# untitled.net
KiCad netlist of a schematic drawn in EAGLE
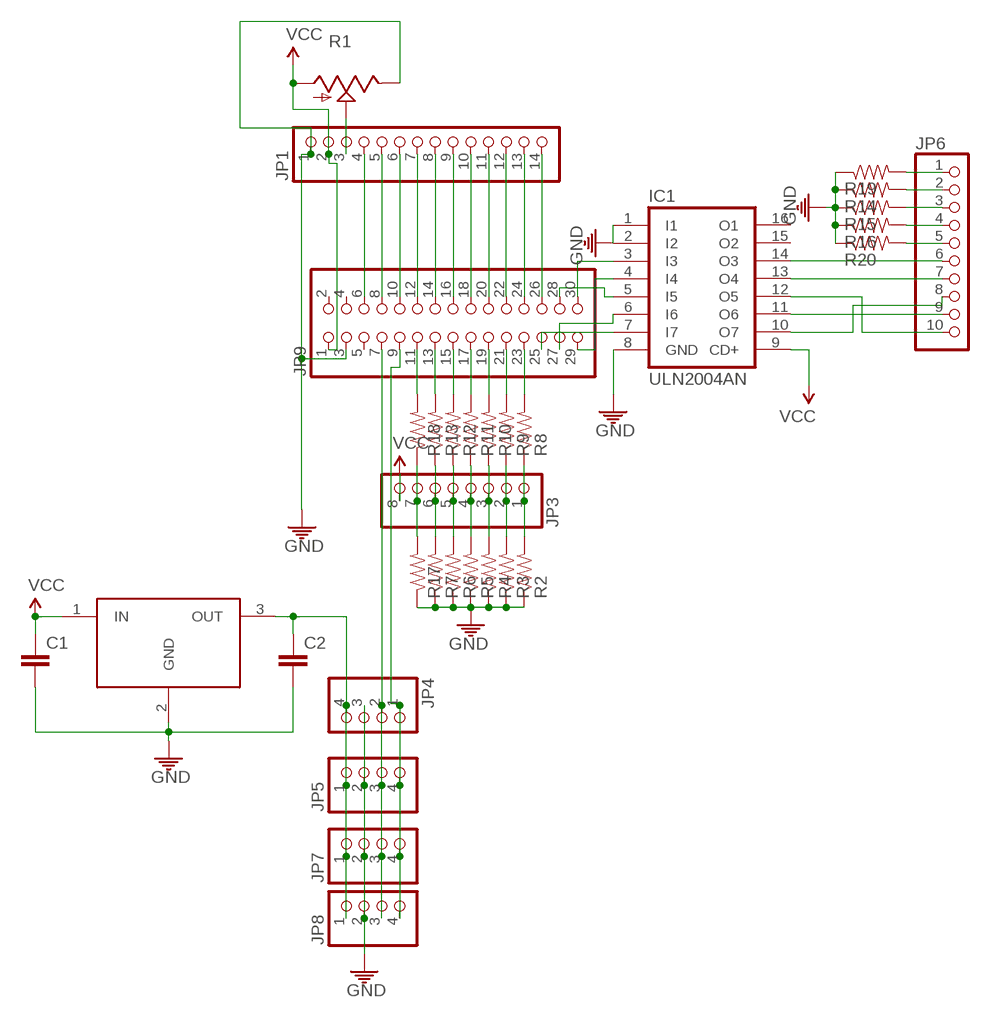
[diagram p0: schematic, sheet 1]

(export (version "E")
  (design (tool "Eeschema 10.0.6"))
  (components
    (comp (ref "C1")
      (value "CAP0805")
      (footprint "eagle-import:0805")
      (libsource (lib "eagle-import") (part "CAP0805"))
    )
    (comp (ref "C2")
      (value "CAP0805")
      (footprint "eagle-import:0805")
      (libsource (lib "eagle-import") (part "CAP0805"))
    )
    (comp (ref "IC1")
      (value "ULN2004AN")
      (footprint "eagle-import:DIL16")
      (libsource (lib "eagle-import") (part "ULN2004AN"))
    )
    (comp (ref "JP1")
      (value "PINHD-1X14")
      (footprint "eagle-import:1X14")
      (libsource (lib "eagle-import") (part "PINHD-1X14"))
    )
    (comp (ref "JP3")
      (value "PINHD-1X8/90")
      (footprint "eagle-import:1X08_90")
      (libsource (lib "eagle-import") (part "PINHD-1X8/90"))
    )
    (comp (ref "JP4")
      (value "PINHD-1X4")
      (footprint "eagle-import:1X04")
      (libsource (lib "eagle-import") (part "PINHD-1X4"))
    )
    (comp (ref "JP5")
      (value "PINHD-1X4")
      (footprint "eagle-import:1X04")
      (libsource (lib "eagle-import") (part "PINHD-1X4"))
    )
    (comp (ref "JP6")
      (value "PINHD-1X10")
      (footprint "eagle-import:1X10")
      (libsource (lib "eagle-import") (part "PINHD-1X10"))
    )
    (comp (ref "JP7")
      (value "PINHD-1X4")
      (footprint "eagle-import:1X04")
      (libsource (lib "eagle-import") (part "PINHD-1X4"))
    )
    (comp (ref "JP8")
      (value "PINHD-1X4")
      (footprint "eagle-import:1X04")
      (libsource (lib "eagle-import") (part "PINHD-1X4"))
    )
    (comp (ref "JP9")
      (value "PINHD-2X15/90")
      (footprint "eagle-import:2X15_90")
      (libsource (lib "eagle-import") (part "PINHD-2X15/90"))
    )
    (comp (ref "R1")
      (value "TRIM_US-B90P")
      (footprint "eagle-import:SP19L")
      (libsource (lib "eagle-import") (part "TRIM_US-B90P"))
    )
    (comp (ref "R2")
      (value "RESISTOR0805-RES")
      (footprint "eagle-import:0805")
      (libsource (lib "eagle-import") (part "RESISTOR0805-RES"))
    )
    (comp (ref "R3")
      (value "RESISTOR0805-RES")
      (footprint "eagle-import:0805")
      (libsource (lib "eagle-import") (part "RESISTOR0805-RES"))
    )
    (comp (ref "R4")
      (value "RESISTOR0805-RES")
      (footprint "eagle-import:0805")
      (libsource (lib "eagle-import") (part "RESISTOR0805-RES"))
    )
    (comp (ref "R5")
      (value "RESISTOR0805-RES")
      (footprint "eagle-import:0805")
      (libsource (lib "eagle-import") (part "RESISTOR0805-RES"))
    )
    (comp (ref "R6")
      (value "RESISTOR0805-RES")
      (footprint "eagle-import:0805")
      (libsource (lib "eagle-import") (part "RESISTOR0805-RES"))
    )
    (comp (ref "R7")
      (value "RESISTOR0805-RES")
      (footprint "eagle-import:0805")
      (libsource (lib "eagle-import") (part "RESISTOR0805-RES"))
    )
    (comp (ref "R8")
      (value "RESISTOR0805-RES")
      (footprint "eagle-import:0805")
      (libsource (lib "eagle-import") (part "RESISTOR0805-RES"))
    )
    (comp (ref "R9")
      (value "RESISTOR0805-RES")
      (footprint "eagle-import:0805")
      (libsource (lib "eagle-import") (part "RESISTOR0805-RES"))
    )
    (comp (ref "R10")
      (value "RESISTOR0805-RES")
      (footprint "eagle-import:0805")
      (libsource (lib "eagle-import") (part "RESISTOR0805-RES"))
    )
    (comp (ref "R11")
      (value "RESISTOR0805-RES")
      (footprint "eagle-import:0805")
      (libsource (lib "eagle-import") (part "RESISTOR0805-RES"))
    )
    (comp (ref "R12")
      (value "RESISTOR0805-RES")
      (footprint "eagle-import:0805")
      (libsource (lib "eagle-import") (part "RESISTOR0805-RES"))
    )
    (comp (ref "R13")
      (value "RESISTOR0805-RES")
      (footprint "eagle-import:0805")
      (libsource (lib "eagle-import") (part "RESISTOR0805-RES"))
    )
    (comp (ref "R14")
      (value "RESISTOR0805-RES")
      (footprint "eagle-import:0805")
      (libsource (lib "eagle-import") (part "RESISTOR0805-RES"))
    )
    (comp (ref "R15")
      (value "RESISTOR0805-RES")
      (footprint "eagle-import:0805")
      (libsource (lib "eagle-import") (part "RESISTOR0805-RES"))
    )
    (comp (ref "R16")
      (value "RESISTOR0805-RES")
      (footprint "eagle-import:0805")
      (libsource (lib "eagle-import") (part "RESISTOR0805-RES"))
    )
    (comp (ref "R17")
      (value "RESISTOR0805-RES")
      (footprint "eagle-import:0805")
      (libsource (lib "eagle-import") (part "RESISTOR0805-RES"))
    )
    (comp (ref "R18")
      (value "RESISTOR0805-RES")
      (footprint "eagle-import:0805")
      (libsource (lib "eagle-import") (part "RESISTOR0805-RES"))
    )
    (comp (ref "R19")
      (value "RESISTOR0805-RES")
      (footprint "eagle-import:0805")
      (libsource (lib "eagle-import") (part "RESISTOR0805-RES"))
    )
    (comp (ref "R20")
      (value "RESISTOR0805-RES")
      (footprint "eagle-import:0805")
      (libsource (lib "eagle-import") (part "RESISTOR0805-RES"))
    )
    (comp (ref "U$5")
      (value "LM3940IMP-3.3")
      (footprint "eagle-import:SOT223")
      (libsource (lib "eagle-import") (part "LM3940IMP-3.3"))
    )
  )
  (nets
    (net (code "1") (name "GND") (class "Default")
      (node (ref "C1") (pin "2") (pinfunction "2_2") (pintype "passive"))
      (node (ref "C2") (pin "2") (pinfunction "2_2") (pintype "passive"))
      (node (ref "IC1") (pin "1") (pinfunction "I1_1") (pintype "input"))
      (node (ref "IC1") (pin "2") (pinfunction "I2_2") (pintype "input"))
      (node (ref "IC1") (pin "8") (pinfunction "GND_8") (pintype "power_in"))
      (node (ref "JP1") (pin "1") (pinfunction "1_1") (pintype "passive"))
      (node (ref "JP4") (pin "3") (pinfunction "3_3") (pintype "passive"))
      (node (ref "JP5") (pin "2") (pinfunction "2_2") (pintype "passive"))
      (node (ref "JP7") (pin "2") (pinfunction "2_2") (pintype "passive"))
      (node (ref "JP8") (pin "2") (pinfunction "2_2") (pintype "passive"))
      (node (ref "JP9") (pin "3") (pinfunction "3_3") (pintype "passive"))
      (node (ref "R1") (pin "E") (pinfunction "E_E") (pintype "passive"))
      (node (ref "R14") (pin "1") (pinfunction "1_1") (pintype "passive"))
      (node (ref "R15") (pin "1") (pinfunction "1_1") (pintype "passive"))
      (node (ref "R16") (pin "1") (pinfunction "1_1") (pintype "passive"))
      (node (ref "R17") (pin "1") (pinfunction "1_1") (pintype "passive"))
      (node (ref "R19") (pin "1") (pinfunction "1_1") (pintype "passive"))
      (node (ref "R2") (pin "1") (pinfunction "1_1") (pintype "passive"))
      (node (ref "R20") (pin "1") (pinfunction "1_1") (pintype "passive"))
      (node (ref "R3") (pin "1") (pinfunction "1_1") (pintype "passive"))
      (node (ref "R4") (pin "1") (pinfunction "1_1") (pintype "passive"))
      (node (ref "R5") (pin "1") (pinfunction "1_1") (pintype "passive"))
      (node (ref "R6") (pin "1") (pinfunction "1_1") (pintype "passive"))
      (node (ref "R7") (pin "1") (pinfunction "1_1") (pintype "passive"))
      (node (ref "U$5") (pin "2") (pinfunction "GND_2") (pintype "power_in"))
    )
    (net (code "2") (name "Net-(IC1-I3)") (class "Default")
      (node (ref "IC1") (pin "3") (pinfunction "I3_3") (pintype "input"))
      (node (ref "JP9") (pin "30") (pinfunction "30_30") (pintype "passive"))
    )
    (net (code "3") (name "Net-(IC1-I4)") (class "Default")
      (node (ref "IC1") (pin "4") (pinfunction "I4_4") (pintype "input"))
      (node (ref "JP9") (pin "29") (pinfunction "29_29") (pintype "passive"))
    )
    (net (code "4") (name "Net-(IC1-I5)") (class "Default")
      (node (ref "IC1") (pin "5") (pinfunction "I5_5") (pintype "input"))
      (node (ref "JP9") (pin "28") (pinfunction "28_28") (pintype "passive"))
    )
    (net (code "5") (name "Net-(IC1-I6)") (class "Default")
      (node (ref "IC1") (pin "6") (pinfunction "I6_6") (pintype "input"))
      (node (ref "JP9") (pin "27") (pinfunction "27_27") (pintype "passive"))
    )
    (net (code "6") (name "Net-(IC1-I7)") (class "Default")
      (node (ref "IC1") (pin "7") (pinfunction "I7_7") (pintype "input"))
      (node (ref "JP9") (pin "25") (pinfunction "25_25") (pintype "passive"))
    )
    (net (code "7") (name "Net-(IC1-O3)") (class "Default")
      (node (ref "IC1") (pin "14") (pinfunction "O3_14") (pintype "open_collector"))
      (node (ref "JP6") (pin "6") (pinfunction "6_6") (pintype "passive"))
    )
    (net (code "8") (name "Net-(IC1-O4)") (class "Default")
      (node (ref "IC1") (pin "13") (pinfunction "O4_13") (pintype "open_collector"))
      (node (ref "JP6") (pin "7") (pinfunction "7_7") (pintype "passive"))
    )
    (net (code "9") (name "Net-(IC1-O5)") (class "Default")
      (node (ref "IC1") (pin "12") (pinfunction "O5_12") (pintype "open_collector"))
      (node (ref "JP6") (pin "10") (pinfunction "10_10") (pintype "passive"))
    )
    (net (code "10") (name "Net-(IC1-O6)") (class "Default")
      (node (ref "IC1") (pin "11") (pinfunction "O6_11") (pintype "open_collector"))
      (node (ref "JP6") (pin "9") (pinfunction "9_9") (pintype "passive"))
    )
    (net (code "11") (name "Net-(IC1-O7)") (class "Default")
      (node (ref "IC1") (pin "10") (pinfunction "O7_10") (pintype "open_collector"))
      (node (ref "JP6") (pin "8") (pinfunction "8_8") (pintype "passive"))
    )
    (net (code "12") (name "Net-(JP1-Pad3)") (class "Default")
      (node (ref "JP1") (pin "3") (pinfunction "3_3") (pintype "passive"))
      (node (ref "R1") (pin "S") (pinfunction "S_S") (pintype "passive"))
    )
    (net (code "13") (name "Net-(JP1-Pad4)") (class "Default")
      (node (ref "JP1") (pin "4") (pinfunction "4_4") (pintype "passive"))
      (node (ref "JP9") (pin "6") (pinfunction "6_6") (pintype "passive"))
    )
    (net (code "14") (name "Net-(JP1-Pad5)") (class "Default")
      (node (ref "JP1") (pin "5") (pinfunction "5_5") (pintype "passive"))
      (node (ref "JP9") (pin "8") (pinfunction "8_8") (pintype "passive"))
    )
    (net (code "15") (name "Net-(JP1-Pad6)") (class "Default")
      (node (ref "JP1") (pin "6") (pinfunction "6_6") (pintype "passive"))
      (node (ref "JP9") (pin "10") (pinfunction "10_10") (pintype "passive"))
    )
    (net (code "16") (name "Net-(JP1-Pad7)") (class "Default")
      (node (ref "JP1") (pin "7") (pinfunction "7_7") (pintype "passive"))
      (node (ref "JP9") (pin "12") (pinfunction "12_12") (pintype "passive"))
    )
    (net (code "17") (name "Net-(JP1-Pad8)") (class "Default")
      (node (ref "JP1") (pin "8") (pinfunction "8_8") (pintype "passive"))
      (node (ref "JP9") (pin "14") (pinfunction "14_14") (pintype "passive"))
    )
    (net (code "18") (name "Net-(JP1-Pad9)") (class "Default")
      (node (ref "JP1") (pin "9") (pinfunction "9_9") (pintype "passive"))
      (node (ref "JP9") (pin "16") (pinfunction "16_16") (pintype "passive"))
    )
    (net (code "19") (name "Net-(JP1-Pad10)") (class "Default")
      (node (ref "JP1") (pin "10") (pinfunction "10_10") (pintype "passive"))
      (node (ref "JP9") (pin "18") (pinfunction "18_18") (pintype "passive"))
    )
    (net (code "20") (name "Net-(JP1-Pad11)") (class "Default")
      (node (ref "JP1") (pin "11") (pinfunction "11_11") (pintype "passive"))
      (node (ref "JP9") (pin "20") (pinfunction "20_20") (pintype "passive"))
    )
    (net (code "21") (name "Net-(JP1-Pad12)") (class "Default")
      (node (ref "JP1") (pin "12") (pinfunction "12_12") (pintype "passive"))
      (node (ref "JP9") (pin "22") (pinfunction "22_22") (pintype "passive"))
    )
    (net (code "22") (name "Net-(JP1-Pad13)") (class "Default")
      (node (ref "JP1") (pin "13") (pinfunction "13_13") (pintype "passive"))
      (node (ref "JP9") (pin "24") (pinfunction "24_24") (pintype "passive"))
    )
    (net (code "23") (name "Net-(JP1-Pad14)") (class "Default")
      (node (ref "JP1") (pin "14") (pinfunction "14_14") (pintype "passive"))
      (node (ref "JP9") (pin "26") (pinfunction "26_26") (pintype "passive"))
    )
    (net (code "24") (name "Net-(JP3-Pad1)") (class "Default")
      (node (ref "JP3") (pin "1") (pinfunction "1_1") (pintype "passive"))
      (node (ref "R2") (pin "2") (pinfunction "2_2") (pintype "passive"))
      (node (ref "R8") (pin "1") (pinfunction "1_1") (pintype "passive"))
    )
    (net (code "25") (name "Net-(JP3-Pad2)") (class "Default")
      (node (ref "JP3") (pin "2") (pinfunction "2_2") (pintype "passive"))
      (node (ref "R3") (pin "2") (pinfunction "2_2") (pintype "passive"))
      (node (ref "R9") (pin "1") (pinfunction "1_1") (pintype "passive"))
    )
    (net (code "26") (name "Net-(JP3-Pad3)") (class "Default")
      (node (ref "JP3") (pin "3") (pinfunction "3_3") (pintype "passive"))
      (node (ref "R10") (pin "1") (pinfunction "1_1") (pintype "passive"))
      (node (ref "R4") (pin "2") (pinfunction "2_2") (pintype "passive"))
    )
    (net (code "27") (name "Net-(JP3-Pad4)") (class "Default")
      (node (ref "JP3") (pin "4") (pinfunction "4_4") (pintype "passive"))
      (node (ref "R11") (pin "1") (pinfunction "1_1") (pintype "passive"))
      (node (ref "R5") (pin "2") (pinfunction "2_2") (pintype "passive"))
    )
    (net (code "28") (name "Net-(JP3-Pad5)") (class "Default")
      (node (ref "JP3") (pin "5") (pinfunction "5_5") (pintype "passive"))
      (node (ref "R12") (pin "1") (pinfunction "1_1") (pintype "passive"))
      (node (ref "R6") (pin "2") (pinfunction "2_2") (pintype "passive"))
    )
    (net (code "29") (name "Net-(JP3-Pad6)") (class "Default")
      (node (ref "JP3") (pin "6") (pinfunction "6_6") (pintype "passive"))
      (node (ref "R13") (pin "1") (pinfunction "1_1") (pintype "passive"))
      (node (ref "R7") (pin "2") (pinfunction "2_2") (pintype "passive"))
    )
    (net (code "30") (name "Net-(JP3-Pad7)") (class "Default")
      (node (ref "JP3") (pin "7") (pinfunction "7_7") (pintype "passive"))
      (node (ref "R17") (pin "2") (pinfunction "2_2") (pintype "passive"))
      (node (ref "R18") (pin "1") (pinfunction "1_1") (pintype "passive"))
    )
    (net (code "31") (name "Net-(JP4-Pad1)") (class "Default")
      (node (ref "JP4") (pin "1") (pinfunction "1_1") (pintype "passive"))
      (node (ref "JP5") (pin "4") (pinfunction "4_4") (pintype "passive"))
      (node (ref "JP7") (pin "4") (pinfunction "4_4") (pintype "passive"))
      (node (ref "JP8") (pin "4") (pinfunction "4_4") (pintype "passive"))
      (node (ref "JP9") (pin "9") (pinfunction "9_9") (pintype "passive"))
    )
    (net (code "32") (name "Net-(JP4-Pad2)") (class "Default")
      (node (ref "JP4") (pin "2") (pinfunction "2_2") (pintype "passive"))
      (node (ref "JP5") (pin "3") (pinfunction "3_3") (pintype "passive"))
      (node (ref "JP7") (pin "3") (pinfunction "3_3") (pintype "passive"))
      (node (ref "JP8") (pin "3") (pinfunction "3_3") (pintype "passive"))
      (node (ref "JP9") (pin "7") (pinfunction "7_7") (pintype "passive"))
    )
    (net (code "33") (name "Net-(JP6-Pad1)") (class "Default")
      (node (ref "JP6") (pin "1") (pinfunction "1_1") (pintype "passive"))
      (node (ref "R19") (pin "2") (pinfunction "2_2") (pintype "passive"))
    )
    (net (code "34") (name "Net-(JP6-Pad2)") (class "Default")
      (node (ref "JP6") (pin "2") (pinfunction "2_2") (pintype "passive"))
      (node (ref "R14") (pin "2") (pinfunction "2_2") (pintype "passive"))
    )
    (net (code "35") (name "Net-(JP6-Pad3)") (class "Default")
      (node (ref "JP6") (pin "3") (pinfunction "3_3") (pintype "passive"))
      (node (ref "R15") (pin "2") (pinfunction "2_2") (pintype "passive"))
    )
    (net (code "36") (name "Net-(JP6-Pad4)") (class "Default")
      (node (ref "JP6") (pin "4") (pinfunction "4_4") (pintype "passive"))
      (node (ref "R16") (pin "2") (pinfunction "2_2") (pintype "passive"))
    )
    (net (code "37") (name "Net-(JP6-Pad5)") (class "Default")
      (node (ref "JP6") (pin "5") (pinfunction "5_5") (pintype "passive"))
      (node (ref "R20") (pin "2") (pinfunction "2_2") (pintype "passive"))
    )
    (net (code "38") (name "Net-(JP9-Pad11)") (class "Default")
      (node (ref "JP9") (pin "11") (pinfunction "11_11") (pintype "passive"))
      (node (ref "R18") (pin "2") (pinfunction "2_2") (pintype "passive"))
    )
    (net (code "39") (name "Net-(JP9-Pad13)") (class "Default")
      (node (ref "JP9") (pin "13") (pinfunction "13_13") (pintype "passive"))
      (node (ref "R13") (pin "2") (pinfunction "2_2") (pintype "passive"))
    )
    (net (code "40") (name "Net-(JP9-Pad15)") (class "Default")
      (node (ref "JP9") (pin "15") (pinfunction "15_15") (pintype "passive"))
      (node (ref "R12") (pin "2") (pinfunction "2_2") (pintype "passive"))
    )
    (net (code "41") (name "Net-(JP9-Pad17)") (class "Default")
      (node (ref "JP9") (pin "17") (pinfunction "17_17") (pintype "passive"))
      (node (ref "R11") (pin "2") (pinfunction "2_2") (pintype "passive"))
    )
    (net (code "42") (name "Net-(JP9-Pad19)") (class "Default")
      (node (ref "JP9") (pin "19") (pinfunction "19_19") (pintype "passive"))
      (node (ref "R10") (pin "2") (pinfunction "2_2") (pintype "passive"))
    )
    (net (code "43") (name "Net-(JP9-Pad21)") (class "Default")
      (node (ref "JP9") (pin "21") (pinfunction "21_21") (pintype "passive"))
      (node (ref "R9") (pin "2") (pinfunction "2_2") (pintype "passive"))
    )
    (net (code "44") (name "Net-(JP9-Pad23)") (class "Default")
      (node (ref "JP9") (pin "23") (pinfunction "23_23") (pintype "passive"))
      (node (ref "R8") (pin "2") (pinfunction "2_2") (pintype "passive"))
    )
    (net (code "45") (name "Net-(U$5-OUT)") (class "Default")
      (node (ref "C2") (pin "1") (pinfunction "1_1") (pintype "passive"))
      (node (ref "JP4") (pin "4") (pinfunction "4_4") (pintype "passive"))
      (node (ref "JP5") (pin "1") (pinfunction "1_1") (pintype "passive"))
      (node (ref "JP7") (pin "1") (pinfunction "1_1") (pintype "passive"))
      (node (ref "JP8") (pin "1") (pinfunction "1_1") (pintype "passive"))
      (node (ref "U$5") (pin "3") (pinfunction "OUT_3") (pintype "power_in"))
    )
    (net (code "46") (name "VCC") (class "Default")
      (node (ref "C1") (pin "1") (pinfunction "1_1") (pintype "passive"))
      (node (ref "IC1") (pin "9") (pinfunction "CD+_9") (pintype "passive"))
      (node (ref "JP1") (pin "2") (pinfunction "2_2") (pintype "passive"))
      (node (ref "JP3") (pin "8") (pinfunction "8_8") (pintype "passive"))
      (node (ref "JP9") (pin "1") (pinfunction "1_1") (pintype "passive"))
      (node (ref "R1") (pin "A") (pinfunction "A_A") (pintype "passive"))
      (node (ref "U$5") (pin "1") (pinfunction "IN_1") (pintype "power_in"))
    )
    (net (code "47") (name "unconnected-(IC1-O1-Pad16)") (class "Default")
      (node (ref "IC1") (pin "16") (pinfunction "O1_16") (pintype "open_collector"))
    )
    (net (code "48") (name "unconnected-(IC1-O2-Pad15)") (class "Default")
      (node (ref "IC1") (pin "15") (pinfunction "O2_15") (pintype "open_collector"))
    )
    (net (code "49") (name "unconnected-(JP9-Pad2)") (class "Default")
      (node (ref "JP9") (pin "2") (pinfunction "2_2") (pintype "passive"))
    )
    (net (code "50") (name "unconnected-(JP9-Pad4)") (class "Default")
      (node (ref "JP9") (pin "4") (pinfunction "4_4") (pintype "passive"))
    )
    (net (code "51") (name "unconnected-(JP9-Pad5)") (class "Default")
      (node (ref "JP9") (pin "5") (pinfunction "5_5") (pintype "passive"))
    )
  )
)
